# Routerv1_2.net
KiCad netlist of a schematic drawn in EAGLE
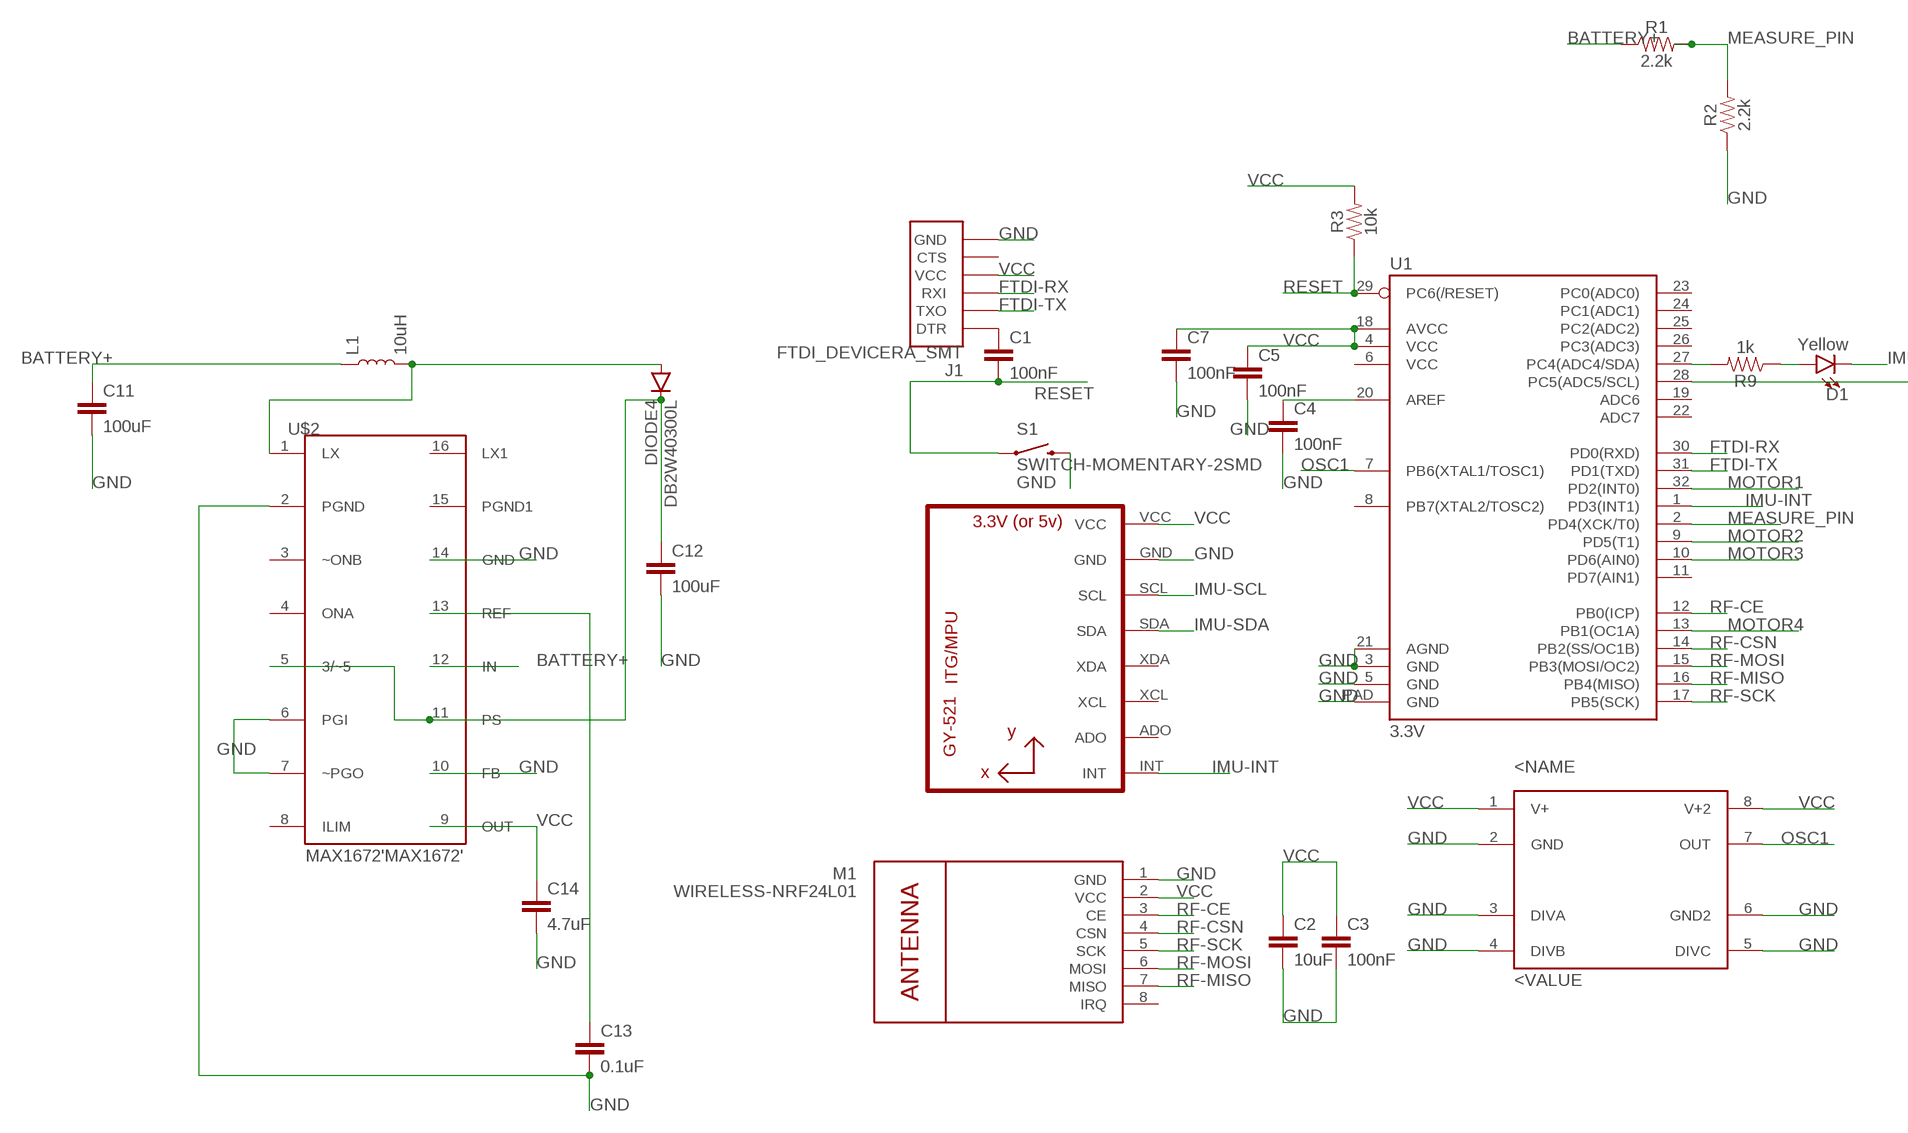
[diagram p0: schematic, sheet 1, part 1 of 2]
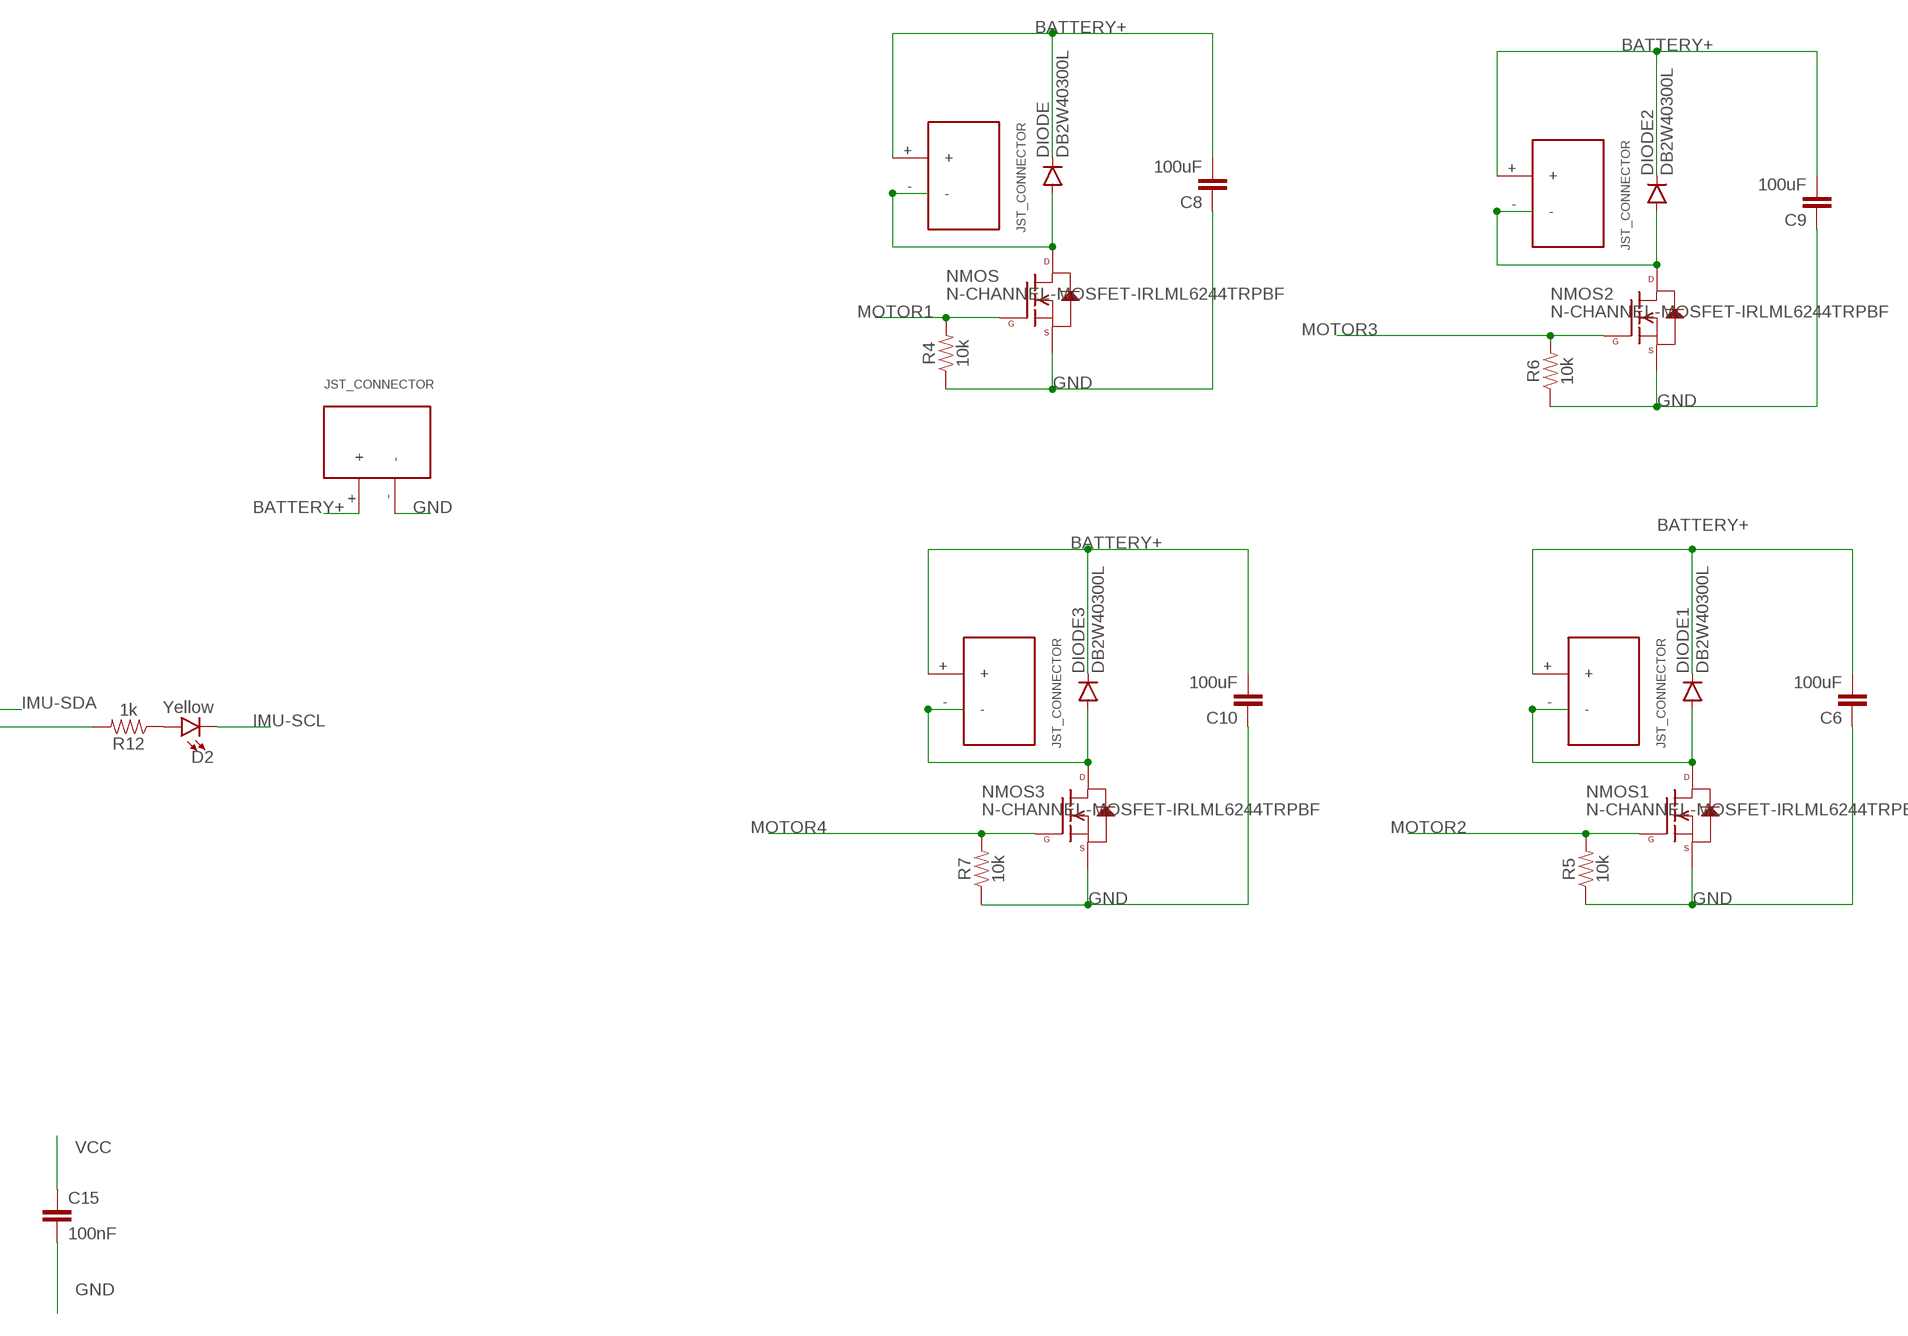
[diagram p1: schematic, sheet 1, part 2 of 2]

(export (version "E")
  (design (tool "Eeschema 10.0.6"))
  (components
    (comp (ref "C1")
      (value "100nF")
      (footprint "eagle-import:0603-CAP")
      (libsource (lib "eagle-import") (part "0.1UF-25V(+80/-20%)(0603)"))
    )
    (comp (ref "C2")
      (value "10uF")
      (footprint "eagle-import:0603-CAP")
      (libsource (lib "eagle-import") (part "CAP0603-CAP"))
    )
    (comp (ref "C3")
      (value "100nF")
      (footprint "eagle-import:0603-CAP")
      (libsource (lib "eagle-import") (part "CAP0603-CAP"))
    )
    (comp (ref "C4")
      (value "100nF")
      (footprint "eagle-import:0603-CAP")
      (libsource (lib "eagle-import") (part "CAP0603-CAP"))
    )
    (comp (ref "C5")
      (value "100nF")
      (footprint "eagle-import:0603-CAP")
      (libsource (lib "eagle-import") (part "CAP0603-CAP"))
    )
    (comp (ref "C6")
      (value "100uF")
      (footprint "eagle-import:0603-CAP")
      (libsource (lib "eagle-import") (part "CAP0603-CAP"))
    )
    (comp (ref "C7")
      (value "100nF")
      (footprint "eagle-import:0603-CAP")
      (libsource (lib "eagle-import") (part "CAP0603-CAP"))
    )
    (comp (ref "C8")
      (value "100uF")
      (footprint "eagle-import:0603-CAP")
      (libsource (lib "eagle-import") (part "CAP0603-CAP"))
    )
    (comp (ref "C9")
      (value "100uF")
      (footprint "eagle-import:0603-CAP")
      (libsource (lib "eagle-import") (part "CAP0603-CAP"))
    )
    (comp (ref "C10")
      (value "100uF")
      (footprint "eagle-import:0603-CAP")
      (libsource (lib "eagle-import") (part "CAP0603-CAP"))
    )
    (comp (ref "C11")
      (value "100uF")
      (footprint "eagle-import:0603-CAP")
      (libsource (lib "eagle-import") (part "CAP0603-CAP"))
    )
    (comp (ref "C12")
      (value "100uF")
      (footprint "eagle-import:0603-CAP")
      (libsource (lib "eagle-import") (part "CAP0603-CAP"))
    )
    (comp (ref "C13")
      (value "0.1uF")
      (footprint "eagle-import:0603-CAP")
      (libsource (lib "eagle-import") (part "CAP0603-CAP"))
    )
    (comp (ref "C14")
      (value "4.7uF")
      (footprint "eagle-import:0603-CAP")
      (libsource (lib "eagle-import") (part "CAP0603-CAP"))
    )
    (comp (ref "C15")
      (value "100nF")
      (footprint "eagle-import:0603-CAP")
      (libsource (lib "eagle-import") (part "0.1UF-25V(+80/-20%)(0603)"))
    )
    (comp (ref "D1")
      (value "Yellow")
      (footprint "eagle-import:LED-1206")
      (libsource (lib "eagle-import") (part "LED-YELLOWLILYPAD"))
    )
    (comp (ref "D2")
      (value "Yellow")
      (footprint "eagle-import:LED-1206")
      (libsource (lib "eagle-import") (part "LED-YELLOWLILYPAD"))
    )
    (comp (ref "DIODE")
      (value "DB2W40300L")
      (footprint "eagle-import:MINI2-F3-B")
      (libsource (lib "eagle-import") (part "DB2W40300L"))
    )
    (comp (ref "DIODE1")
      (value "DB2W40300L")
      (footprint "eagle-import:MINI2-F3-B")
      (libsource (lib "eagle-import") (part "DB2W40300L"))
    )
    (comp (ref "DIODE2")
      (value "DB2W40300L")
      (footprint "eagle-import:MINI2-F3-B")
      (libsource (lib "eagle-import") (part "DB2W40300L"))
    )
    (comp (ref "DIODE3")
      (value "DB2W40300L")
      (footprint "eagle-import:MINI2-F3-B")
      (libsource (lib "eagle-import") (part "DB2W40300L"))
    )
    (comp (ref "DIODE4")
      (value "DB2W40300L")
      (footprint "eagle-import:MINI2-F3-B")
      (libsource (lib "eagle-import") (part "DB2W40300L"))
    )
    (comp (ref "J1")
      (value "FTDI_DEVICERA_SMT")
      (footprint "eagle-import:FTDI_DEVICE_RA_SMT")
      (libsource (lib "eagle-import") (part "FTDI_DEVICERA_SMT"))
    )
    (comp (ref "L1")
      (value "10uH")
      (footprint "eagle-import:0603")
      (libsource (lib "eagle-import") (part "INDUCTOR-0603-33NH"))
    )
    (comp (ref "M1")
      (value "WIRELESS-NRF24L01")
      (footprint "eagle-import:WIRELESS-NRF24L01")
      (libsource (lib "eagle-import") (part "WIRELESS-NRF24L01"))
    )
    (comp (ref "MOTOR")
      (value "JST_CONNECTOR_FEMALE")
      (footprint "eagle-import:JST_CONNECTOR_FEMALE")
      (libsource (lib "eagle-import") (part "JST_CONNECTOR_FEMALE"))
    )
    (comp (ref "MOTOR1")
      (value "JST_CONNECTOR_FEMALE")
      (footprint "eagle-import:JST_CONNECTOR_FEMALE")
      (libsource (lib "eagle-import") (part "JST_CONNECTOR_FEMALE"))
    )
    (comp (ref "MOTOR2")
      (value "JST_CONNECTOR_FEMALE")
      (footprint "eagle-import:JST_CONNECTOR_FEMALE")
      (libsource (lib "eagle-import") (part "JST_CONNECTOR_FEMALE"))
    )
    (comp (ref "MOTOR3")
      (value "JST_CONNECTOR_FEMALE")
      (footprint "eagle-import:JST_CONNECTOR_FEMALE")
      (libsource (lib "eagle-import") (part "JST_CONNECTOR_FEMALE"))
    )
    (comp (ref "NMOS")
      (value "N-CHANNEL-MOSFET-IRLML6244TRPBF")
      (footprint "eagle-import:SOT23-3")
      (libsource (lib "eagle-import") (part "N-CHANNEL-MOSFET-IRLML6244TRPBF"))
    )
    (comp (ref "NMOS1")
      (value "N-CHANNEL-MOSFET-IRLML6244TRPBF")
      (footprint "eagle-import:SOT23-3")
      (libsource (lib "eagle-import") (part "N-CHANNEL-MOSFET-IRLML6244TRPBF"))
    )
    (comp (ref "NMOS2")
      (value "N-CHANNEL-MOSFET-IRLML6244TRPBF")
      (footprint "eagle-import:SOT23-3")
      (libsource (lib "eagle-import") (part "N-CHANNEL-MOSFET-IRLML6244TRPBF"))
    )
    (comp (ref "NMOS3")
      (value "N-CHANNEL-MOSFET-IRLML6244TRPBF")
      (footprint "eagle-import:SOT23-3")
      (libsource (lib "eagle-import") (part "N-CHANNEL-MOSFET-IRLML6244TRPBF"))
    )
    (comp (ref "R1")
      (value "2.2k")
      (footprint "eagle-import:0603")
      (libsource (lib "eagle-import") (part "2.2KOHM-0603-1/10W-1%"))
    )
    (comp (ref "R2")
      (value "2.2k")
      (footprint "eagle-import:0603")
      (libsource (lib "eagle-import") (part "2.2KOHM-0603-1/10W-1%"))
    )
    (comp (ref "R3")
      (value "10k")
      (footprint "eagle-import:0603")
      (libsource (lib "eagle-import") (part "2.2KOHM-0603-1/10W-1%"))
    )
    (comp (ref "R4")
      (value "10k")
      (footprint "eagle-import:0603")
      (libsource (lib "eagle-import") (part "2.2KOHM-0603-1/10W-1%"))
    )
    (comp (ref "R5")
      (value "10k")
      (footprint "eagle-import:0603")
      (libsource (lib "eagle-import") (part "2.2KOHM-0603-1/10W-1%"))
    )
    (comp (ref "R6")
      (value "10k")
      (footprint "eagle-import:0603")
      (libsource (lib "eagle-import") (part "2.2KOHM-0603-1/10W-1%"))
    )
    (comp (ref "R7")
      (value "10k")
      (footprint "eagle-import:0603")
      (libsource (lib "eagle-import") (part "2.2KOHM-0603-1/10W-1%"))
    )
    (comp (ref "R9")
      (value "1k")
      (footprint "eagle-import:0603")
      (libsource (lib "eagle-import") (part "2.2KOHM-0603-1/10W-1%"))
    )
    (comp (ref "R12")
      (value "1k")
      (footprint "eagle-import:0603")
      (libsource (lib "eagle-import") (part "2.2KOHM-0603-1/10W-1%"))
    )
    (comp (ref "S1")
      (value "SWITCH-MOMENTARY-2SMD")
      (footprint "eagle-import:TACTILE-SWITCH-SMD")
      (libsource (lib "eagle-import") (part "SWITCH-MOMENTARY-2SMD"))
    )
    (comp (ref "U$1")
      (value "JST_CONNECTOR_FEMALE")
      (footprint "eagle-import:JST_CONNECTOR_FEMALE")
      (libsource (lib "eagle-import") (part "JST_CONNECTOR_FEMALE"))
    )
    (comp (ref "U$2")
      (value "MAX1672'MAX1672'")
      (footprint "eagle-import:21-0055H_16")
      (libsource (lib "eagle-import") (part "MAX1672'MAX1672'"))
    )
    (comp (ref "U$3")
      (value "LTC6930CMS8-8.19LTC6930CMS8-8.19")
      (footprint "eagle-import:SOP65P490X110-8N")
      (libsource (lib "eagle-import") (part "LTC6930CMS8-8.19LTC6930CMS8-8.19"))
    )
    (comp (ref "U1")
      (value "3.3V")
      (footprint "eagle-import:MLF32-PAD")
      (libsource (lib "eagle-import") (part "ATMEGA328P_MLFMLF32"))
    )
    (comp (ref "U2")
      (value "GY-521MPU6050")
      (footprint "eagle-import:GY-521")
      (libsource (lib "eagle-import") (part "GY-521MPU6050"))
    )
  )
  (nets
    (net (code "1") (name "BATTERY+") (class "Default")
      (node (ref "C10") (pin "2") (pinfunction "2_2") (pintype "passive"))
      (node (ref "C11") (pin "1") (pinfunction "1_1") (pintype "passive"))
      (node (ref "C6") (pin "2") (pinfunction "2_2") (pintype "passive"))
      (node (ref "C8") (pin "2") (pinfunction "2_2") (pintype "passive"))
      (node (ref "C9") (pin "2") (pinfunction "2_2") (pintype "passive"))
      (node (ref "DIODE") (pin "NEG") (pinfunction "GPIN_NEG") (pintype "passive"))
      (node (ref "DIODE1") (pin "NEG") (pinfunction "GPIN_NEG") (pintype "passive"))
      (node (ref "DIODE2") (pin "NEG") (pinfunction "GPIN_NEG") (pintype "passive"))
      (node (ref "DIODE3") (pin "NEG") (pinfunction "GPIN_NEG") (pintype "passive"))
      (node (ref "L1") (pin "1") (pinfunction "1_1") (pintype "passive"))
      (node (ref "MOTOR") (pin "+") (pinfunction "+_+") (pintype "bidirectional"))
      (node (ref "MOTOR1") (pin "+") (pinfunction "+_+") (pintype "bidirectional"))
      (node (ref "MOTOR2") (pin "+") (pinfunction "+_+") (pintype "bidirectional"))
      (node (ref "MOTOR3") (pin "+") (pinfunction "+_+") (pintype "bidirectional"))
      (node (ref "R1") (pin "1") (pinfunction "1_1") (pintype "passive"))
      (node (ref "U$1") (pin "+") (pinfunction "+_+") (pintype "bidirectional"))
      (node (ref "U$2") (pin "12") (pinfunction "IN_12") (pintype "bidirectional"))
    )
    (net (code "2") (name "FTDI-RX") (class "Default")
      (node (ref "J1") (pin "3") (pinfunction "RXI_3") (pintype "bidirectional"))
      (node (ref "U1") (pin "30") (pinfunction "PD0(RXD)_30") (pintype "bidirectional"))
    )
    (net (code "3") (name "FTDI-TX") (class "Default")
      (node (ref "J1") (pin "2") (pinfunction "TXO_2") (pintype "bidirectional"))
      (node (ref "U1") (pin "31") (pinfunction "PD1(TXD)_31") (pintype "bidirectional"))
    )
    (net (code "4") (name "GND") (class "Default")
      (node (ref "C10") (pin "1") (pinfunction "1_1") (pintype "passive"))
      (node (ref "C11") (pin "2") (pinfunction "2_2") (pintype "passive"))
      (node (ref "C12") (pin "2") (pinfunction "2_2") (pintype "passive"))
      (node (ref "C13") (pin "2") (pinfunction "2_2") (pintype "passive"))
      (node (ref "C14") (pin "2") (pinfunction "2_2") (pintype "passive"))
      (node (ref "C15") (pin "2") (pinfunction "2_2") (pintype "passive"))
      (node (ref "C2") (pin "2") (pinfunction "2_2") (pintype "passive"))
      (node (ref "C3") (pin "2") (pinfunction "2_2") (pintype "passive"))
      (node (ref "C4") (pin "2") (pinfunction "2_2") (pintype "passive"))
      (node (ref "C5") (pin "2") (pinfunction "2_2") (pintype "passive"))
      (node (ref "C6") (pin "1") (pinfunction "1_1") (pintype "passive"))
      (node (ref "C7") (pin "2") (pinfunction "2_2") (pintype "passive"))
      (node (ref "C8") (pin "1") (pinfunction "1_1") (pintype "passive"))
      (node (ref "C9") (pin "1") (pinfunction "1_1") (pintype "passive"))
      (node (ref "J1") (pin "6") (pinfunction "GND_6") (pintype "bidirectional"))
      (node (ref "M1") (pin "1") (pinfunction "GND_1") (pintype "power_in"))
      (node (ref "NMOS") (pin "2") (pinfunction "S_2") (pintype "passive"))
      (node (ref "NMOS1") (pin "2") (pinfunction "S_2") (pintype "passive"))
      (node (ref "NMOS2") (pin "2") (pinfunction "S_2") (pintype "passive"))
      (node (ref "NMOS3") (pin "2") (pinfunction "S_2") (pintype "passive"))
      (node (ref "R2") (pin "1") (pinfunction "1_1") (pintype "passive"))
      (node (ref "R4") (pin "1") (pinfunction "1_1") (pintype "passive"))
      (node (ref "R5") (pin "1") (pinfunction "1_1") (pintype "passive"))
      (node (ref "R6") (pin "1") (pinfunction "1_1") (pintype "passive"))
      (node (ref "R7") (pin "1") (pinfunction "1_1") (pintype "passive"))
      (node (ref "S1") (pin "3") (pinfunction "2_3") (pintype "passive"))
      (node (ref "U$1") (pin "-") (pinfunction "-_-") (pintype "bidirectional"))
      (node (ref "U$2") (pin "10") (pinfunction "FB_10") (pintype "bidirectional"))
      (node (ref "U$2") (pin "14") (pinfunction "GND_14") (pintype "bidirectional"))
      (node (ref "U$2") (pin "2") (pinfunction "PGND_2") (pintype "bidirectional"))
      (node (ref "U$2") (pin "6") (pinfunction "PGI_6") (pintype "bidirectional"))
      (node (ref "U$2") (pin "7") (pinfunction "~{PGO}_7") (pintype "bidirectional"))
      (node (ref "U$3") (pin "2") (pinfunction "GND_2") (pintype "bidirectional"))
      (node (ref "U$3") (pin "3") (pinfunction "DIVA_3") (pintype "bidirectional"))
      (node (ref "U$3") (pin "4") (pinfunction "DIVB_4") (pintype "bidirectional"))
      (node (ref "U$3") (pin "5") (pinfunction "DIVC_5") (pintype "bidirectional"))
      (node (ref "U$3") (pin "6") (pinfunction "GND2_6") (pintype "bidirectional"))
      (node (ref "U1") (pin "21") (pinfunction "AGND_21") (pintype "bidirectional"))
      (node (ref "U1") (pin "3") (pinfunction "GND_3") (pintype "bidirectional"))
      (node (ref "U1") (pin "5") (pinfunction "GND_5") (pintype "bidirectional"))
      (node (ref "U1") (pin "PAD") (pinfunction "GND_PAD") (pintype "bidirectional"))
      (node (ref "U2") (pin "GND") (pinfunction "GND_GND") (pintype "bidirectional"))
    )
    (net (code "5") (name "IMU-INT") (class "Default")
      (node (ref "U1") (pin "1") (pinfunction "PD3(INT1)_1") (pintype "bidirectional"))
      (node (ref "U2") (pin "INT") (pinfunction "INT_INT") (pintype "bidirectional"))
    )
    (net (code "6") (name "IMU-SCL") (class "Default")
      (node (ref "D2") (pin "C") (pinfunction "C_C") (pintype "passive"))
      (node (ref "U2") (pin "SCL") (pinfunction "SCL_SCL") (pintype "bidirectional"))
    )
    (net (code "7") (name "IMU-SDA") (class "Default")
      (node (ref "D1") (pin "C") (pinfunction "C_C") (pintype "passive"))
      (node (ref "U2") (pin "SDA") (pinfunction "SDA_SDA") (pintype "bidirectional"))
    )
    (net (code "8") (name "MEASURE_PIN") (class "Default")
      (node (ref "R1") (pin "2") (pinfunction "2_2") (pintype "passive"))
      (node (ref "R2") (pin "2") (pinfunction "2_2") (pintype "passive"))
      (node (ref "U1") (pin "2") (pinfunction "PD4(XCK/T0)_2") (pintype "bidirectional"))
    )
    (net (code "9") (name "MOTOR1") (class "Default")
      (node (ref "NMOS") (pin "1") (pinfunction "G_1") (pintype "passive"))
      (node (ref "R4") (pin "2") (pinfunction "2_2") (pintype "passive"))
      (node (ref "U1") (pin "32") (pinfunction "PD2(INT0)_32") (pintype "bidirectional"))
    )
    (net (code "10") (name "MOTOR2") (class "Default")
      (node (ref "NMOS1") (pin "1") (pinfunction "G_1") (pintype "passive"))
      (node (ref "R5") (pin "2") (pinfunction "2_2") (pintype "passive"))
      (node (ref "U1") (pin "9") (pinfunction "PD5(T1)_9") (pintype "bidirectional"))
    )
    (net (code "11") (name "MOTOR3") (class "Default")
      (node (ref "NMOS2") (pin "1") (pinfunction "G_1") (pintype "passive"))
      (node (ref "R6") (pin "2") (pinfunction "2_2") (pintype "passive"))
      (node (ref "U1") (pin "10") (pinfunction "PD6(AIN0)_10") (pintype "bidirectional"))
    )
    (net (code "12") (name "MOTOR4") (class "Default")
      (node (ref "NMOS3") (pin "1") (pinfunction "G_1") (pintype "passive"))
      (node (ref "R7") (pin "2") (pinfunction "2_2") (pintype "passive"))
      (node (ref "U1") (pin "13") (pinfunction "PB1(OC1A)_13") (pintype "bidirectional"))
    )
    (net (code "13") (name "Net-(D1-PadA)") (class "Default")
      (node (ref "D1") (pin "A") (pinfunction "A_A") (pintype "passive"))
      (node (ref "R9") (pin "1") (pinfunction "1_1") (pintype "passive"))
    )
    (net (code "14") (name "Net-(D2-PadA)") (class "Default")
      (node (ref "D2") (pin "A") (pinfunction "A_A") (pintype "passive"))
      (node (ref "R12") (pin "1") (pinfunction "1_1") (pintype "passive"))
    )
    (net (code "15") (name "Net-(DIODE-PPIN)") (class "Default")
      (node (ref "DIODE") (pin "POS") (pinfunction "PPIN_POS") (pintype "passive"))
      (node (ref "MOTOR") (pin "-") (pinfunction "-_-") (pintype "bidirectional"))
      (node (ref "NMOS") (pin "3") (pinfunction "D_3") (pintype "passive"))
    )
    (net (code "16") (name "Net-(DIODE1-PPIN)") (class "Default")
      (node (ref "DIODE1") (pin "POS") (pinfunction "PPIN_POS") (pintype "passive"))
      (node (ref "MOTOR1") (pin "-") (pinfunction "-_-") (pintype "bidirectional"))
      (node (ref "NMOS1") (pin "3") (pinfunction "D_3") (pintype "passive"))
    )
    (net (code "17") (name "Net-(DIODE2-PPIN)") (class "Default")
      (node (ref "DIODE2") (pin "POS") (pinfunction "PPIN_POS") (pintype "passive"))
      (node (ref "MOTOR2") (pin "-") (pinfunction "-_-") (pintype "bidirectional"))
      (node (ref "NMOS2") (pin "3") (pinfunction "D_3") (pintype "passive"))
    )
    (net (code "18") (name "Net-(DIODE3-PPIN)") (class "Default")
      (node (ref "DIODE3") (pin "POS") (pinfunction "PPIN_POS") (pintype "passive"))
      (node (ref "MOTOR3") (pin "-") (pinfunction "-_-") (pintype "bidirectional"))
      (node (ref "NMOS3") (pin "3") (pinfunction "D_3") (pintype "passive"))
    )
    (net (code "19") (name "Net-(DIODE4-GPIN)") (class "Default")
      (node (ref "C12") (pin "1") (pinfunction "1_1") (pintype "passive"))
      (node (ref "DIODE4") (pin "NEG") (pinfunction "GPIN_NEG") (pintype "passive"))
      (node (ref "U$2") (pin "11") (pinfunction "PS_11") (pintype "bidirectional"))
      (node (ref "U$2") (pin "5") (pinfunction "3/~{5}_5") (pintype "bidirectional"))
    )
    (net (code "20") (name "Net-(DIODE4-PPIN)") (class "Default")
      (node (ref "DIODE4") (pin "POS") (pinfunction "PPIN_POS") (pintype "passive"))
      (node (ref "L1") (pin "2") (pinfunction "2_2") (pintype "passive"))
      (node (ref "U$2") (pin "1") (pinfunction "LX_1") (pintype "bidirectional"))
    )
    (net (code "21") (name "Net-(J1-DTR)") (class "Default")
      (node (ref "C1") (pin "1") (pinfunction "1_1") (pintype "passive"))
      (node (ref "J1") (pin "1") (pinfunction "DTR_1") (pintype "bidirectional"))
    )
    (net (code "22") (name "Net-(U$2-REF)") (class "Default")
      (node (ref "C13") (pin "1") (pinfunction "1_1") (pintype "passive"))
      (node (ref "U$2") (pin "13") (pinfunction "REF_13") (pintype "bidirectional"))
    )
    (net (code "23") (name "Net-(U1-AREF)") (class "Default")
      (node (ref "C4") (pin "1") (pinfunction "1_1") (pintype "passive"))
      (node (ref "U1") (pin "20") (pinfunction "AREF_20") (pintype "bidirectional"))
    )
    (net (code "24") (name "Net-(U1-PC4(ADC4{slash}SDA))") (class "Default")
      (node (ref "R9") (pin "2") (pinfunction "2_2") (pintype "passive"))
      (node (ref "U1") (pin "27") (pinfunction "PC4(ADC4/SDA)_27") (pintype "bidirectional"))
    )
    (net (code "25") (name "Net-(U1-PC5(ADC5{slash}SCL))") (class "Default")
      (node (ref "R12") (pin "2") (pinfunction "2_2") (pintype "passive"))
      (node (ref "U1") (pin "28") (pinfunction "PC5(ADC5/SCL)_28") (pintype "bidirectional"))
    )
    (net (code "26") (name "OSC1") (class "Default")
      (node (ref "U$3") (pin "7") (pinfunction "OUT_7") (pintype "bidirectional"))
      (node (ref "U1") (pin "7") (pinfunction "PB6(XTAL1/TOSC1)_7") (pintype "bidirectional"))
    )
    (net (code "27") (name "RESET") (class "Default")
      (node (ref "C1") (pin "2") (pinfunction "2_2") (pintype "passive"))
      (node (ref "R3") (pin "1") (pinfunction "1_1") (pintype "passive"))
      (node (ref "S1") (pin "1") (pinfunction "1_1") (pintype "passive"))
      (node (ref "U1") (pin "29") (pinfunction "PC6(/RESET)_29") (pintype "bidirectional"))
    )
    (net (code "28") (name "RF-CE") (class "Default")
      (node (ref "M1") (pin "3") (pinfunction "CE_3") (pintype "bidirectional"))
      (node (ref "U1") (pin "12") (pinfunction "PB0(ICP)_12") (pintype "bidirectional"))
    )
    (net (code "29") (name "RF-CSN") (class "Default")
      (node (ref "M1") (pin "4") (pinfunction "CSN_4") (pintype "bidirectional"))
      (node (ref "U1") (pin "14") (pinfunction "PB2(SS/OC1B)_14") (pintype "bidirectional"))
    )
    (net (code "30") (name "RF-MISO") (class "Default")
      (node (ref "M1") (pin "7") (pinfunction "MISO_7") (pintype "bidirectional"))
      (node (ref "U1") (pin "16") (pinfunction "PB4(MISO)_16") (pintype "bidirectional"))
    )
    (net (code "31") (name "RF-MOSI") (class "Default")
      (node (ref "M1") (pin "6") (pinfunction "MOSI_6") (pintype "bidirectional"))
      (node (ref "U1") (pin "15") (pinfunction "PB3(MOSI/OC2)_15") (pintype "bidirectional"))
    )
    (net (code "32") (name "RF-SCK") (class "Default")
      (node (ref "M1") (pin "5") (pinfunction "SCK_5") (pintype "bidirectional"))
      (node (ref "U1") (pin "17") (pinfunction "PB5(SCK)_17") (pintype "bidirectional"))
    )
    (net (code "33") (name "VCC") (class "Default")
      (node (ref "C14") (pin "1") (pinfunction "1_1") (pintype "passive"))
      (node (ref "C15") (pin "1") (pinfunction "1_1") (pintype "passive"))
      (node (ref "C2") (pin "1") (pinfunction "1_1") (pintype "passive"))
      (node (ref "C3") (pin "1") (pinfunction "1_1") (pintype "passive"))
      (node (ref "C5") (pin "1") (pinfunction "1_1") (pintype "passive"))
      (node (ref "C7") (pin "1") (pinfunction "1_1") (pintype "passive"))
      (node (ref "J1") (pin "4") (pinfunction "VCC_4") (pintype "bidirectional"))
      (node (ref "M1") (pin "2") (pinfunction "VCC_2") (pintype "power_in"))
      (node (ref "R3") (pin "2") (pinfunction "2_2") (pintype "passive"))
      (node (ref "U$2") (pin "9") (pinfunction "OUT_9") (pintype "bidirectional"))
      (node (ref "U$3") (pin "1") (pinfunction "V+_1") (pintype "bidirectional"))
      (node (ref "U$3") (pin "8") (pinfunction "V+2_8") (pintype "bidirectional"))
      (node (ref "U1") (pin "18") (pinfunction "AVCC_18") (pintype "bidirectional"))
      (node (ref "U1") (pin "4") (pinfunction "VCC_4") (pintype "bidirectional"))
      (node (ref "U2") (pin "VCC") (pinfunction "VCC_VCC") (pintype "bidirectional"))
    )
    (net (code "34") (name "unconnected-(J1-CTS-Pad5)") (class "Default")
      (node (ref "J1") (pin "5") (pinfunction "CTS_5") (pintype "bidirectional"))
    )
    (net (code "35") (name "unconnected-(M1-IRQ-Pad8)") (class "Default")
      (node (ref "M1") (pin "8") (pinfunction "IRQ_8") (pintype "bidirectional"))
    )
    (net (code "36") (name "unconnected-(U$2-ILIM-Pad8)") (class "Default")
      (node (ref "U$2") (pin "8") (pinfunction "ILIM_8") (pintype "bidirectional"))
    )
    (net (code "37") (name "unconnected-(U$2-LX1-Pad16)") (class "Default")
      (node (ref "U$2") (pin "16") (pinfunction "LX1_16") (pintype "bidirectional"))
    )
    (net (code "38") (name "unconnected-(U$2-ONA-Pad4)") (class "Default")
      (node (ref "U$2") (pin "4") (pinfunction "ONA_4") (pintype "bidirectional"))
    )
    (net (code "39") (name "unconnected-(U$2-PGND1-Pad15)") (class "Default")
      (node (ref "U$2") (pin "15") (pinfunction "PGND1_15") (pintype "bidirectional"))
    )
    (net (code "40") (name "unconnected-(U$2-~{ONB}-Pad3)") (class "Default")
      (node (ref "U$2") (pin "3") (pinfunction "~{ONB}_3") (pintype "bidirectional"))
    )
    (net (code "41") (name "unconnected-(U1-ADC6-Pad19)") (class "Default")
      (node (ref "U1") (pin "19") (pinfunction "ADC6_19") (pintype "bidirectional"))
    )
    (net (code "42") (name "unconnected-(U1-ADC7-Pad22)") (class "Default")
      (node (ref "U1") (pin "22") (pinfunction "ADC7_22") (pintype "bidirectional"))
    )
    (net (code "43") (name "unconnected-(U1-PB7(XTAL2{slash}TOSC2)-Pad8)") (class "Default")
      (node (ref "U1") (pin "8") (pinfunction "PB7(XTAL2/TOSC2)_8") (pintype "bidirectional"))
    )
    (net (code "44") (name "unconnected-(U1-PC0(ADC0)-Pad23)") (class "Default")
      (node (ref "U1") (pin "23") (pinfunction "PC0(ADC0)_23") (pintype "bidirectional"))
    )
    (net (code "45") (name "unconnected-(U1-PC1(ADC1)-Pad24)") (class "Default")
      (node (ref "U1") (pin "24") (pinfunction "PC1(ADC1)_24") (pintype "bidirectional"))
    )
    (net (code "46") (name "unconnected-(U1-PC2(ADC2)-Pad25)") (class "Default")
      (node (ref "U1") (pin "25") (pinfunction "PC2(ADC2)_25") (pintype "bidirectional"))
    )
    (net (code "47") (name "unconnected-(U1-PC3(ADC3)-Pad26)") (class "Default")
      (node (ref "U1") (pin "26") (pinfunction "PC3(ADC3)_26") (pintype "bidirectional"))
    )
    (net (code "48") (name "unconnected-(U1-PD7(AIN1)-Pad11)") (class "Default")
      (node (ref "U1") (pin "11") (pinfunction "PD7(AIN1)_11") (pintype "bidirectional"))
    )
    (net (code "49") (name "unconnected-(U1-VCC-Pad6)") (class "Default")
      (node (ref "U1") (pin "6") (pinfunction "VCC_6") (pintype "bidirectional"))
    )
    (net (code "50") (name "unconnected-(U2-PadADO)") (class "Default")
      (node (ref "U2") (pin "ADO") (pinfunction "ADO_ADO") (pintype "bidirectional"))
    )
    (net (code "51") (name "unconnected-(U2-PadXCL)") (class "Default")
      (node (ref "U2") (pin "XCL") (pinfunction "XCL_XCL") (pintype "bidirectional"))
    )
    (net (code "52") (name "unconnected-(U2-PadXDA)") (class "Default")
      (node (ref "U2") (pin "XDA") (pinfunction "XDA_XDA") (pintype "bidirectional"))
    )
  )
)
